# PIC32MZ.net
KiCad netlist of a schematic drawn in Altium Designer
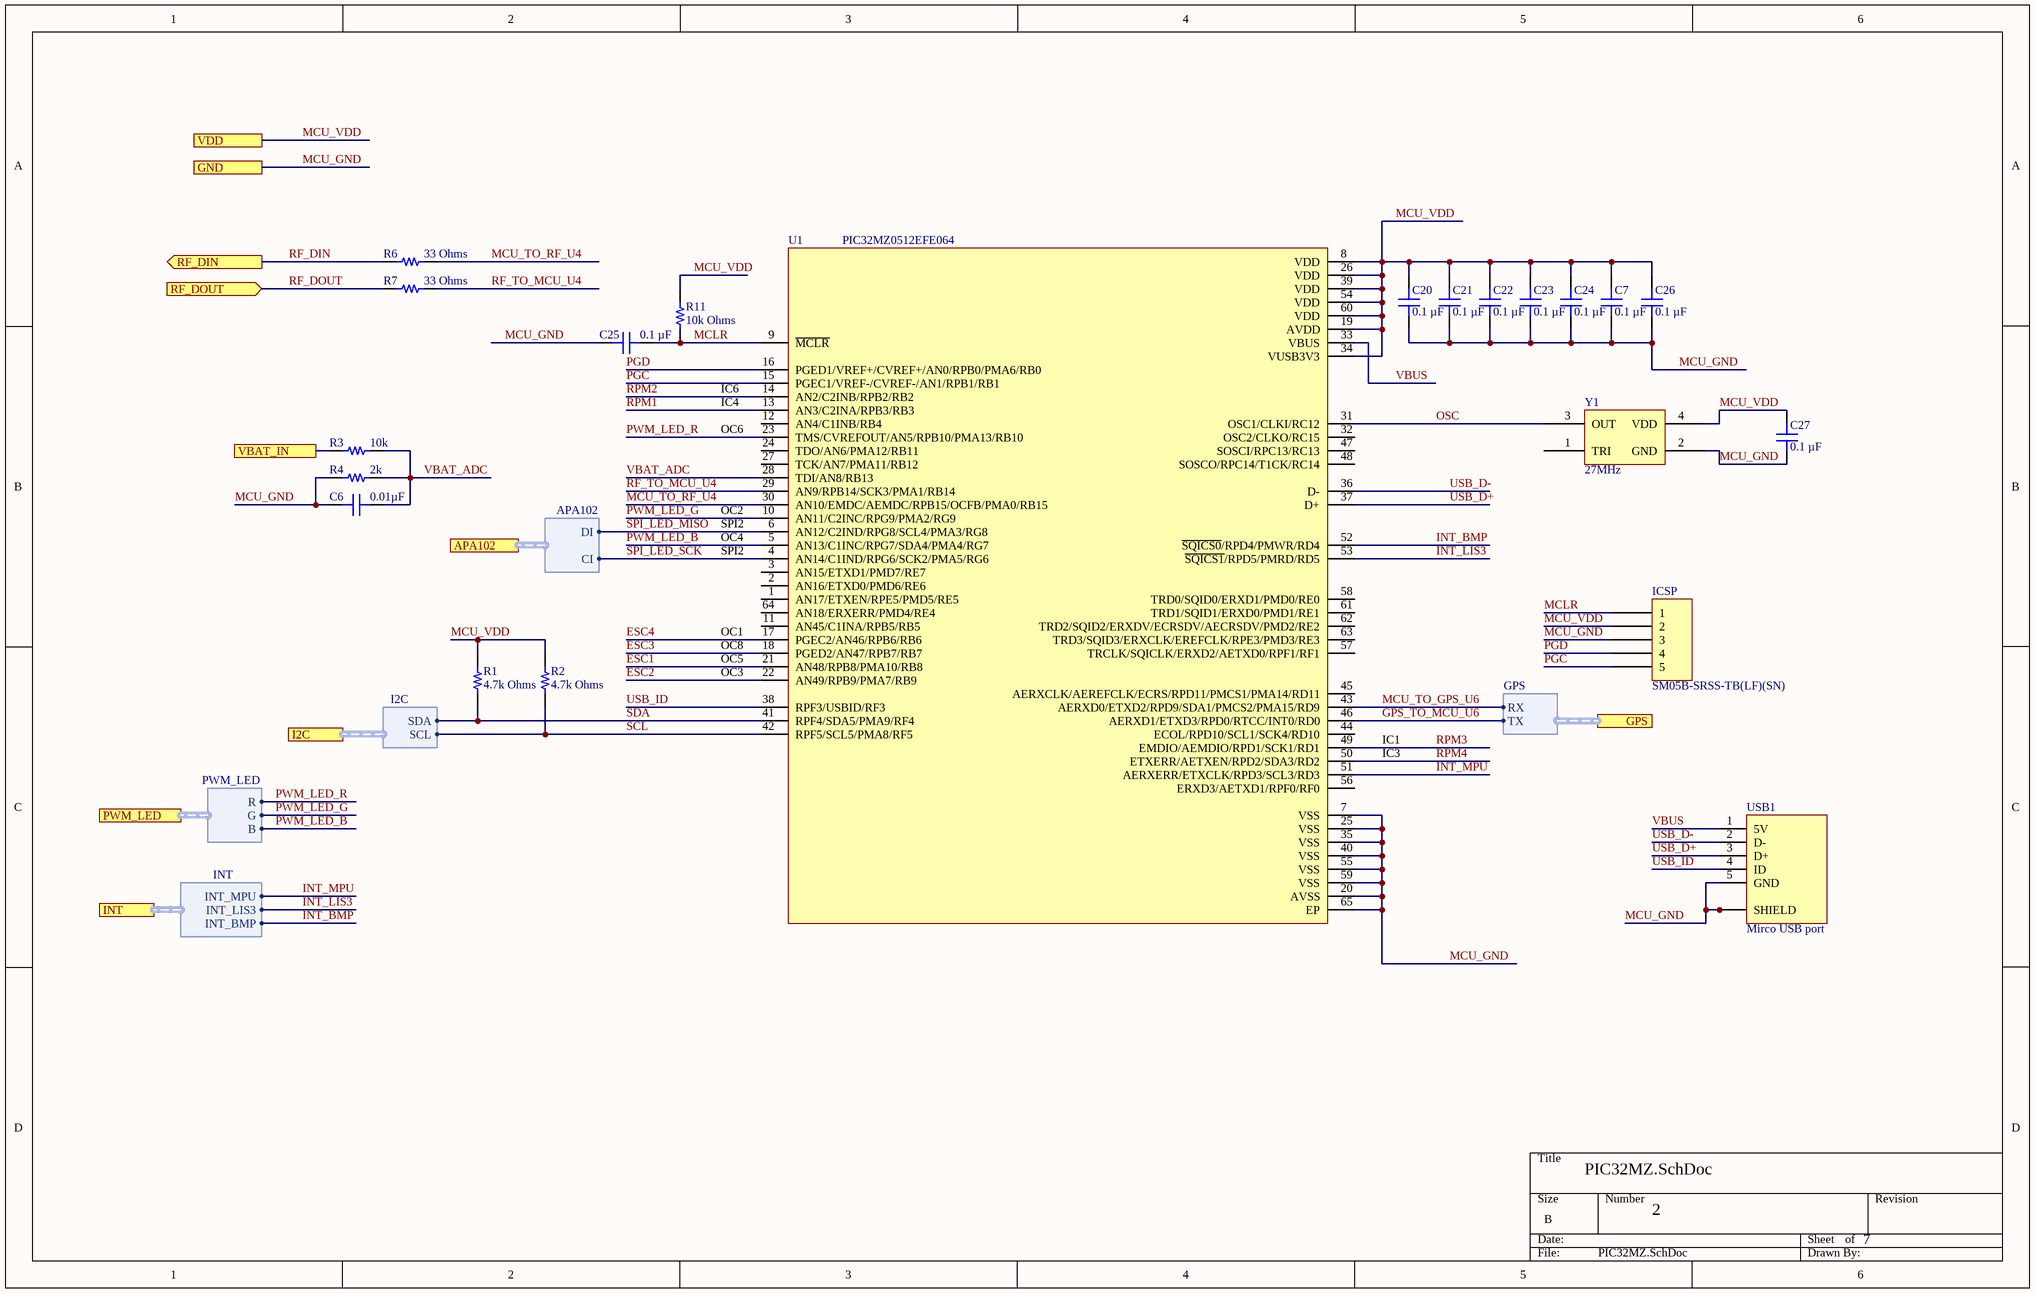
[diagram p0: PIC32MZ.SchDoc]

(export (version "E")
  (design (tool "Eeschema 10.0.6"))
  (components
    (comp (ref "C6")
      (value "0.01µF")
      (footprint "CAP 0603_1608")
      (description "CAP CER 0.1UF 100V 0603 EPOXY")
      (fields
        (field (name "PART NUMBER") "GCG188R92A104KA03D")
        (field (name "MANUFACTURER") "Murata Electronics")
      )
      (libsource (lib "Celestial Altium Library - altium_library") (part "Capacitor"))
    )
    (comp (ref "C7")
      (value "0.1 µF")
      (footprint "CAP 0402_1005")
      (description "CAP CER 0.1UF 16V X7R 0402")
      (fields (field (name "PART NUMBER") "C0402C104K4RACAUTO") (field (name "MANUFACTURER") "KEMET"))
      (libsource (lib "Celestial Altium Library - altium_library") (part "Capacitor"))
    )
    (comp (ref "C20")
      (value "0.1 µF")
      (footprint "CAP 0402_1005")
      (description "CAP CER 0.1UF 16V X7R 0402")
      (fields (field (name "PART NUMBER") "C0402C104K4RACAUTO") (field (name "MANUFACTURER") "KEMET"))
      (libsource (lib "Celestial Altium Library - altium_library") (part "Capacitor"))
    )
    (comp (ref "C21")
      (value "0.1 µF")
      (footprint "CAP 0402_1005")
      (description "CAP CER 0.1UF 16V X7R 0402")
      (fields (field (name "PART NUMBER") "C0402C104K4RACAUTO") (field (name "MANUFACTURER") "KEMET"))
      (libsource (lib "Celestial Altium Library - altium_library") (part "Capacitor"))
    )
    (comp (ref "C22")
      (value "0.1 µF")
      (footprint "CAP 0402_1005")
      (description "CAP CER 0.1UF 16V X7R 0402")
      (fields (field (name "PART NUMBER") "C0402C104K4RACAUTO") (field (name "MANUFACTURER") "KEMET"))
      (libsource (lib "Celestial Altium Library - altium_library") (part "Capacitor"))
    )
    (comp (ref "C23")
      (value "0.1 µF")
      (footprint "CAP 0402_1005")
      (description "CAP CER 0.1UF 16V X7R 0402")
      (fields (field (name "PART NUMBER") "C0402C104K4RACAUTO") (field (name "MANUFACTURER") "KEMET"))
      (libsource (lib "Celestial Altium Library - altium_library") (part "Capacitor"))
    )
    (comp (ref "C24")
      (value "0.1 µF")
      (footprint "CAP 0402_1005")
      (description "CAP CER 0.1UF 16V X7R 0402")
      (fields (field (name "PART NUMBER") "C0402C104K4RACAUTO") (field (name "MANUFACTURER") "KEMET"))
      (libsource (lib "Celestial Altium Library - altium_library") (part "Capacitor"))
    )
    (comp (ref "C25")
      (value "0.1 µF")
      (footprint "CAP 0402_1005")
      (description "CAP CER 0.1UF 16V X7R 0402")
      (fields (field (name "PART NUMBER") "C0402C104K4RACAUTO") (field (name "MANUFACTURER") "KEMET"))
      (libsource (lib "Celestial Altium Library - altium_library") (part "Capacitor"))
    )
    (comp (ref "C26")
      (value "0.1 µF")
      (footprint "CAP 0402_1005")
      (description "CAP CER 0.1UF 16V X7R 0402")
      (fields (field (name "PART NUMBER") "C0402C104K4RACAUTO") (field (name "MANUFACTURER") "KEMET"))
      (libsource (lib "Celestial Altium Library - altium_library") (part "Capacitor"))
    )
    (comp (ref "C27")
      (value "0.1 µF")
      (footprint "CAP 0402_1005")
      (description "CAP CER 0.1UF 16V X7R 0402")
      (fields (field (name "PART NUMBER") "C0402C104K4RACAUTO") (field (name "MANUFACTURER") "KEMET"))
      (libsource (lib "Celestial Altium Library - altium_library") (part "Capacitor"))
    )
    (comp (ref "ICSP")
      (value "SM05B-SRSS-TB(LF)(SN)")
      (footprint "JST SM05B-SRSS-TB")
      (description "CONN HEADER SMD R/A 5POS 1MM")
      (fields (field (name "MANUFACTURER") "JST Sales America Inc."))
      (libsource (lib "Celestial Altium Library - altium_library") (part "5 Pin"))
    )
    (comp (ref "R1")
      (value "4.7k Ohms")
      (footprint "RES 0402_1005")
      (description "RES 330 OHM 5% 1/16W 0402")
      (fields (field (name "PART NUMBER") "CRCW0402330RJNEDC") (field (name "MANUFACTURER") "Vishay Dale"))
      (libsource (lib "Celestial Altium Library - altium_library") (part "Resistor"))
    )
    (comp (ref "R2")
      (value "4.7k Ohms")
      (footprint "RES 0402_1005")
      (description "RES 330 OHM 5% 1/16W 0402")
      (fields (field (name "PART NUMBER") "CRCW0402330RJNEDC") (field (name "MANUFACTURER") "Vishay Dale"))
      (libsource (lib "Celestial Altium Library - altium_library") (part "Resistor"))
    )
    (comp (ref "R3")
      (value "10k")
      (footprint "RES 0603_1608")
      (description "RES SMD 21.5 OHM 1% 1/10W 0603")
      (fields
        (field (name "PART NUMBER") "ERJ-3EKF21R5V")
        (field (name "MANUFACTURER") "Panasonic Electronic Components")
      )
      (libsource (lib "Celestial Altium Library - altium_library") (part "Resistor"))
    )
    (comp (ref "R4")
      (value "2k")
      (footprint "RES 0603_1608")
      (description "RES SMD 21.5 OHM 1% 1/10W 0603")
      (fields
        (field (name "PART NUMBER") "ERJ-3EKF21R5V")
        (field (name "MANUFACTURER") "Panasonic Electronic Components")
      )
      (libsource (lib "Celestial Altium Library - altium_library") (part "Resistor"))
    )
    (comp (ref "R6")
      (value "33 Ohms")
      (footprint "RES 0402_1005")
      (description "RES 330 OHM 5% 1/16W 0402")
      (fields (field (name "PART NUMBER") "CRCW0402330RJNEDC") (field (name "MANUFACTURER") "Vishay Dale"))
      (libsource (lib "Celestial Altium Library - altium_library") (part "Resistor"))
    )
    (comp (ref "R7")
      (value "33 Ohms")
      (footprint "RES 0402_1005")
      (description "RES 330 OHM 5% 1/16W 0402")
      (fields (field (name "PART NUMBER") "CRCW0402330RJNEDC") (field (name "MANUFACTURER") "Vishay Dale"))
      (libsource (lib "Celestial Altium Library - altium_library") (part "Resistor"))
    )
    (comp (ref "R11")
      (value "10k Ohms")
      (footprint "RES 0402_1005")
      (description "RES 330 OHM 5% 1/16W 0402")
      (fields (field (name "PART NUMBER") "CRCW0402330RJNEDC") (field (name "MANUFACTURER") "Vishay Dale"))
      (libsource (lib "Celestial Altium Library - altium_library") (part "Resistor"))
    )
    (comp (ref "U1")
      (value "PIC32MZ0512EFE064")
      (footprint "QFN50P900X900X100-65N")
      (description "32-bit Microcontrollers - MCU 32-BIT MCU 512KB FL 128KB RAM, No Crypto")
      (fields (field (name "MF") "Microchip") (field (name "MP") "PIC32MZ2048EFG064T-I/PT"))
      (libsource (lib "IC") (part "PIC32MZ0512EFE064-I/PT"))
    )
    (comp (ref "USB1")
      (value "Mirco USB port")
      (footprint "AMPHENOL_10118194-0001LF")
      (description "USB - micro B USB 2.0 Receptacle Connector 5 Position Through Hole")
      (fields (field (name "MF") "Amphenol ICC") (field (name "MP") "10118194-0001LF"))
      (libsource (lib "IC") (part "USB Micro Horizontal"))
    )
    (comp (ref "Y1")
      (value "27MHz")
      (footprint "ABRACON ASD")
      (description "XTAL OSC XO 27.0000MHZ HCMOS SMD")
      (fields (field (name "PART NUMBER") "ASD3-27.000MHZ-EC-T") (field (name "MANUFACTURER") "Abracon LLC"))
      (libsource (lib "Celestial Altium Library - altium_library") (part "Abracon XO ASD"))
    )
  )
  (nets
    (net (code "6") (name "/ESC1") (class "Default")
      (node (ref "U1") (pin "21") (pinfunction "AN48/RPB8/PMA10/RB8_21") (pintype "passive"))
    )
    (net (code "7") (name "/ESC2") (class "Default")
      (node (ref "U1") (pin "22") (pinfunction "AN49/RPB9/PMA7/RB9_22") (pintype "passive"))
    )
    (net (code "8") (name "/ESC3") (class "Default")
      (node (ref "U1") (pin "18") (pinfunction "PGED2/AN47/RPB7/RB7_18") (pintype "passive"))
    )
    (net (code "9") (name "/ESC4") (class "Default")
      (node (ref "U1") (pin "17") (pinfunction "PGEC2/AN46/RPB6/RB6_17") (pintype "passive"))
    )
    (net (code "10") (name "/GPS_TO_MCU_U6") (class "Default")
      (node (ref "U1") (pin "46") (pinfunction "AERXD1/ETXD3/RPD0/RTCC/INT0/RD0_46") (pintype "passive"))
    )
    (net (code "11") (name "/INT_BMP") (class "Default")
      (node (ref "U1") (pin "52") (pinfunction "~{SQICS0}/RPD4/PMWR/RD4_52") (pintype "passive"))
    )
    (net (code "12") (name "/INT_LIS3") (class "Default")
      (node (ref "U1") (pin "53") (pinfunction "~{SQICS1}/RPD5/PMRD/RD5_53") (pintype "passive"))
    )
    (net (code "13") (name "/INT_MPU") (class "Default")
      (node (ref "U1") (pin "51") (pinfunction "AERXERR/ETXCLK/RPD3/SCL3/RD3_51") (pintype "passive"))
    )
    (net (code "14") (name "/MCLR") (class "Default")
      (node (ref "C25") (pin "1") (pinfunction "1_1") (pintype "passive"))
      (node (ref "ICSP") (pin "1") (pinfunction "1_1") (pintype "passive"))
      (node (ref "R11") (pin "1") (pinfunction "1_1") (pintype "passive"))
      (node (ref "U1") (pin "9") (pinfunction "~{MCLR}_9") (pintype "passive"))
    )
    (net (code "15") (name "/MCU_GND") (class "Default")
      (node (ref "C20") (pin "1") (pinfunction "1_1") (pintype "passive"))
      (node (ref "C21") (pin "1") (pinfunction "1_1") (pintype "passive"))
      (node (ref "C22") (pin "1") (pinfunction "1_1") (pintype "passive"))
      (node (ref "C23") (pin "1") (pinfunction "1_1") (pintype "passive"))
      (node (ref "C24") (pin "1") (pinfunction "1_1") (pintype "passive"))
      (node (ref "C25") (pin "2") (pinfunction "2_2") (pintype "passive"))
      (node (ref "C26") (pin "1") (pinfunction "1_1") (pintype "passive"))
      (node (ref "C27") (pin "1") (pinfunction "1_1") (pintype "passive"))
      (node (ref "C6") (pin "2") (pinfunction "2_2") (pintype "passive"))
      (node (ref "C7") (pin "1") (pinfunction "1_1") (pintype "passive"))
      (node (ref "ICSP") (pin "3") (pinfunction "3_3") (pintype "passive"))
      (node (ref "R4") (pin "1") (pinfunction "1_1") (pintype "passive"))
      (node (ref "U1") (pin "20") (pinfunction "AVSS_20") (pintype "power_in"))
      (node (ref "U1") (pin "25") (pinfunction "VSS_25") (pintype "power_in"))
      (node (ref "U1") (pin "35") (pinfunction "VSS_35") (pintype "power_in"))
      (node (ref "U1") (pin "40") (pinfunction "VSS_40") (pintype "power_in"))
      (node (ref "U1") (pin "55") (pinfunction "VSS_55") (pintype "power_in"))
      (node (ref "U1") (pin "59") (pinfunction "VSS_59") (pintype "power_in"))
      (node (ref "U1") (pin "65") (pinfunction "EP_65") (pintype "power_in"))
      (node (ref "U1") (pin "7") (pinfunction "VSS_7") (pintype "power_in"))
      (node (ref "USB1") (pin "5") (pinfunction "GND_5") (pintype "passive"))
      (node (ref "USB1") (pin "S1") (pinfunction "SHIELD_S1") (pintype "passive"))
      (node (ref "USB1") (pin "S2") (pinfunction "SHIELD_S2") (pintype "passive"))
      (node (ref "Y1") (pin "2") (pinfunction "GND_2") (pintype "passive"))
    )
    (net (code "16") (name "/MCU_TO_GPS_U6") (class "Default")
      (node (ref "U1") (pin "43") (pinfunction "AERXD0/ETXD2/RPD9/SDA1/PMCS2/PMA15/RD9_43") (pintype "passive"))
    )
    (net (code "17") (name "/MCU_TO_RF_U4") (class "Default")
      (node (ref "R6") (pin "2") (pinfunction "2_2") (pintype "passive"))
      (node (ref "U1") (pin "30") (pinfunction "AN10/EMDC/AEMDC/RPB15/OCFB/PMA0/RB15_30") (pintype "passive"))
    )
    (net (code "18") (name "/MCU_VDD") (class "Default")
      (node (ref "C20") (pin "2") (pinfunction "2_2") (pintype "passive"))
      (node (ref "C21") (pin "2") (pinfunction "2_2") (pintype "passive"))
      (node (ref "C22") (pin "2") (pinfunction "2_2") (pintype "passive"))
      (node (ref "C23") (pin "2") (pinfunction "2_2") (pintype "passive"))
      (node (ref "C24") (pin "2") (pinfunction "2_2") (pintype "passive"))
      (node (ref "C26") (pin "2") (pinfunction "2_2") (pintype "passive"))
      (node (ref "C27") (pin "2") (pinfunction "2_2") (pintype "passive"))
      (node (ref "C7") (pin "2") (pinfunction "2_2") (pintype "passive"))
      (node (ref "ICSP") (pin "2") (pinfunction "2_2") (pintype "passive"))
      (node (ref "R1") (pin "2") (pinfunction "2_2") (pintype "passive"))
      (node (ref "R11") (pin "2") (pinfunction "2_2") (pintype "passive"))
      (node (ref "R2") (pin "2") (pinfunction "2_2") (pintype "passive"))
      (node (ref "U1") (pin "19") (pinfunction "AVDD_19") (pintype "power_in"))
      (node (ref "U1") (pin "26") (pinfunction "VDD_26") (pintype "power_in"))
      (node (ref "U1") (pin "34") (pinfunction "VUSB3V3_34") (pintype "power_in"))
      (node (ref "U1") (pin "39") (pinfunction "VDD_39") (pintype "power_in"))
      (node (ref "U1") (pin "54") (pinfunction "VDD_54") (pintype "power_in"))
      (node (ref "U1") (pin "60") (pinfunction "VDD_60") (pintype "power_in"))
      (node (ref "U1") (pin "8") (pinfunction "VDD_8") (pintype "power_in"))
      (node (ref "Y1") (pin "4") (pinfunction "VDD_4") (pintype "passive"))
    )
    (net (code "19") (name "/OSC") (class "Default")
      (node (ref "U1") (pin "31") (pinfunction "OSC1/CLKI/RC12_31") (pintype "passive"))
      (node (ref "Y1") (pin "3") (pinfunction "OUT_3") (pintype "passive"))
    )
    (net (code "20") (name "/PGC") (class "Default")
      (node (ref "ICSP") (pin "5") (pinfunction "5_5") (pintype "passive"))
      (node (ref "U1") (pin "15") (pinfunction "PGEC1/VREF-/CVREF-/AN1/RPB1/RB1_15") (pintype "passive"))
    )
    (net (code "21") (name "/PGD") (class "Default")
      (node (ref "ICSP") (pin "4") (pinfunction "4_4") (pintype "passive"))
      (node (ref "U1") (pin "16") (pinfunction "PGED1/VREF+/CVREF+/AN0/RPB0/PMA6/RB0_16") (pintype "passive"))
    )
    (net (code "22") (name "/PWM_LED_B") (class "Default")
      (node (ref "U1") (pin "5") (pinfunction "AN13/C1INC/RPG7/SDA4/PMA4/RG7_5") (pintype "passive"))
    )
    (net (code "23") (name "/PWM_LED_G") (class "Default")
      (node (ref "U1") (pin "10") (pinfunction "AN11/C2INC/RPG9/PMA2/RG9_10") (pintype "passive"))
    )
    (net (code "24") (name "/PWM_LED_R") (class "Default")
      (node (ref "U1") (pin "23") (pinfunction "TMS/CVREFOUT/AN5/RPB10/PMA13/RB10_23") (pintype "passive"))
    )
    (net (code "25") (name "/RF_DIN") (class "Default")
      (node (ref "R6") (pin "1") (pinfunction "1_1") (pintype "passive"))
    )
    (net (code "26") (name "/RF_DOUT") (class "Default")
      (node (ref "R7") (pin "1") (pinfunction "1_1") (pintype "passive"))
    )
    (net (code "27") (name "/RF_TO_MCU_U4") (class "Default")
      (node (ref "R7") (pin "2") (pinfunction "2_2") (pintype "passive"))
      (node (ref "U1") (pin "29") (pinfunction "AN9/RPB14/SCK3/PMA1/RB14_29") (pintype "passive"))
    )
    (net (code "28") (name "/RPM1") (class "Default")
      (node (ref "U1") (pin "13") (pinfunction "AN3/C2INA/RPB3/RB3_13") (pintype "passive"))
    )
    (net (code "29") (name "/RPM2") (class "Default")
      (node (ref "U1") (pin "14") (pinfunction "AN2/C2INB/RPB2/RB2_14") (pintype "passive"))
    )
    (net (code "30") (name "/RPM3") (class "Default")
      (node (ref "U1") (pin "49") (pinfunction "EMDIO/AEMDIO/RPD1/SCK1/RD1_49") (pintype "passive"))
    )
    (net (code "31") (name "/RPM4") (class "Default")
      (node (ref "U1") (pin "50") (pinfunction "ETXERR/AETXEN/RPD2/SDA3/RD2_50") (pintype "passive"))
    )
    (net (code "32") (name "/SCL") (class "Default")
      (node (ref "R2") (pin "1") (pinfunction "1_1") (pintype "passive"))
      (node (ref "U1") (pin "42") (pinfunction "RPF5/SCL5/PMA8/RF5_42") (pintype "passive"))
    )
    (net (code "33") (name "/SDA") (class "Default")
      (node (ref "R1") (pin "1") (pinfunction "1_1") (pintype "passive"))
      (node (ref "U1") (pin "41") (pinfunction "RPF4/SDA5/PMA9/RF4_41") (pintype "passive"))
    )
    (net (code "34") (name "/SPI_LED_MISO") (class "Default")
      (node (ref "U1") (pin "6") (pinfunction "AN12/C2IND/RPG8/SCL4/PMA3/RG8_6") (pintype "passive"))
    )
    (net (code "35") (name "/SPI_LED_SCK") (class "Default")
      (node (ref "U1") (pin "4") (pinfunction "AN14/C1IND/RPG6/SCK2/PMA5/RG6_4") (pintype "passive"))
    )
    (net (code "36") (name "/USB_D+") (class "Default")
      (node (ref "U1") (pin "37") (pinfunction "D+_37") (pintype "passive"))
      (node (ref "USB1") (pin "3") (pinfunction "D+_3") (pintype "passive"))
    )
    (net (code "37") (name "/USB_D-") (class "Default")
      (node (ref "U1") (pin "36") (pinfunction "D-_36") (pintype "passive"))
      (node (ref "USB1") (pin "2") (pinfunction "D-_2") (pintype "passive"))
    )
    (net (code "38") (name "/USB_ID") (class "Default")
      (node (ref "U1") (pin "38") (pinfunction "RPF3/USBID/RF3_38") (pintype "passive"))
      (node (ref "USB1") (pin "4") (pinfunction "ID_4") (pintype "passive"))
    )
    (net (code "39") (name "/VBAT_ADC") (class "Default")
      (node (ref "C6") (pin "1") (pinfunction "1_1") (pintype "passive"))
      (node (ref "R3") (pin "1") (pinfunction "1_1") (pintype "passive"))
      (node (ref "R4") (pin "2") (pinfunction "2_2") (pintype "passive"))
      (node (ref "U1") (pin "28") (pinfunction "TDI/AN8/RB13_28") (pintype "passive"))
    )
    (net (code "40") (name "/VBAT_IN") (class "Default")
      (node (ref "R3") (pin "2") (pinfunction "2_2") (pintype "passive"))
    )
    (net (code "41") (name "/VBUS") (class "Default")
      (node (ref "U1") (pin "33") (pinfunction "VBUS_33") (pintype "power_in"))
      (node (ref "USB1") (pin "1") (pinfunction "5V_1") (pintype "passive"))
    )
    (net (code "47") (name "unconnected-(U1-AERXCLK{slash}AEREFCLK{slash}ECRS{slash}RPD11{slash}PMCS1{slash}PMA14{slash}RD11-Pad45)") (class "Default")
      (node (ref "U1") (pin "45") (pinfunction "AERXCLK/AEREFCLK/ECRS/RPD11/PMCS1/PMA14/RD11_45") (pintype "passive"))
    )
    (net (code "48") (name "unconnected-(U1-AN4{slash}C1INB{slash}RB4-Pad12)") (class "Default")
      (node (ref "U1") (pin "12") (pinfunction "AN4/C1INB/RB4_12") (pintype "passive"))
    )
    (net (code "49") (name "unconnected-(U1-AN15{slash}ETXD1{slash}PMD7{slash}RE7-Pad3)") (class "Default")
      (node (ref "U1") (pin "3") (pinfunction "AN15/ETXD1/PMD7/RE7_3") (pintype "passive"))
    )
    (net (code "50") (name "unconnected-(U1-AN16{slash}ETXD0{slash}PMD6{slash}RE6-Pad2)") (class "Default")
      (node (ref "U1") (pin "2") (pinfunction "AN16/ETXD0/PMD6/RE6_2") (pintype "passive"))
    )
    (net (code "51") (name "unconnected-(U1-AN17{slash}ETXEN{slash}RPE5{slash}PMD5{slash}RE5-Pad1)") (class "Default")
      (node (ref "U1") (pin "1") (pinfunction "AN17/ETXEN/RPE5/PMD5/RE5_1") (pintype "passive"))
    )
    (net (code "52") (name "unconnected-(U1-AN18{slash}ERXERR{slash}PMD4{slash}RE4-Pad64)") (class "Default")
      (node (ref "U1") (pin "64") (pinfunction "AN18/ERXERR/PMD4/RE4_64") (pintype "passive"))
    )
    (net (code "53") (name "unconnected-(U1-AN45{slash}C1INA{slash}RPB5{slash}RB5-Pad11)") (class "Default")
      (node (ref "U1") (pin "11") (pinfunction "AN45/C1INA/RPB5/RB5_11") (pintype "passive"))
    )
    (net (code "54") (name "unconnected-(U1-ECOL{slash}RPD10{slash}SCL1{slash}SCK4{slash}RD10-Pad44)") (class "Default")
      (node (ref "U1") (pin "44") (pinfunction "ECOL/RPD10/SCL1/SCK4/RD10_44") (pintype "passive"))
    )
    (net (code "55") (name "unconnected-(U1-ERXD3{slash}AETXD1{slash}RPF0{slash}RF0-Pad56)") (class "Default")
      (node (ref "U1") (pin "56") (pinfunction "ERXD3/AETXD1/RPF0/RF0_56") (pintype "passive"))
    )
    (net (code "56") (name "unconnected-(U1-OSC2{slash}CLKO{slash}RC15-Pad32)") (class "Default")
      (node (ref "U1") (pin "32") (pinfunction "OSC2/CLKO/RC15_32") (pintype "passive"))
    )
    (net (code "57") (name "unconnected-(U1-SOSCI{slash}RPC13{slash}RC13-Pad47)") (class "Default")
      (node (ref "U1") (pin "47") (pinfunction "SOSCI/RPC13/RC13_47") (pintype "passive"))
    )
    (net (code "58") (name "unconnected-(U1-SOSCO{slash}RPC14{slash}T1CK{slash}RC14-Pad48)") (class "Default")
      (node (ref "U1") (pin "48") (pinfunction "SOSCO/RPC14/T1CK/RC14_48") (pintype "passive"))
    )
    (net (code "59") (name "unconnected-(U1-TCK{slash}AN7{slash}PMA11{slash}RB12-Pad27)") (class "Default")
      (node (ref "U1") (pin "27") (pinfunction "TCK/AN7/PMA11/RB12_27") (pintype "passive"))
    )
    (net (code "60") (name "unconnected-(U1-TDO{slash}AN6{slash}PMA12{slash}RB11-Pad24)") (class "Default")
      (node (ref "U1") (pin "24") (pinfunction "TDO/AN6/PMA12/RB11_24") (pintype "passive"))
    )
    (net (code "61") (name "unconnected-(U1-TRCLK{slash}SQICLK{slash}ERXD2{slash}AETXD0{slash}RPF1{slash}RF1-Pad57)") (class "Default")
      (node (ref "U1") (pin "57") (pinfunction "TRCLK/SQICLK/ERXD2/AETXD0/RPF1/RF1_57") (pintype "passive"))
    )
    (net (code "62") (name "unconnected-(U1-TRD0{slash}SQID0{slash}ERXD1{slash}PMD0{slash}RE0-Pad58)") (class "Default")
      (node (ref "U1") (pin "58") (pinfunction "TRD0/SQID0/ERXD1/PMD0/RE0_58") (pintype "passive"))
    )
    (net (code "63") (name "unconnected-(U1-TRD1{slash}SQID1{slash}ERXD0{slash}PMD1{slash}RE1-Pad61)") (class "Default")
      (node (ref "U1") (pin "61") (pinfunction "TRD1/SQID1/ERXD0/PMD1/RE1_61") (pintype "passive"))
    )
    (net (code "64") (name "unconnected-(U1-TRD2{slash}SQID2{slash}ERXDV{slash}ECRSDV{slash}AECRSDV{slash}PMD2{slash}RE2-Pad62)") (class "Default")
      (node (ref "U1") (pin "62") (pinfunction "TRD2/SQID2/ERXDV/ECRSDV/AECRSDV/PMD2/RE2_62") (pintype "passive"))
    )
    (net (code "65") (name "unconnected-(U1-TRD3{slash}SQID3{slash}ERXCLK{slash}EREFCLK{slash}RPE3{slash}PMD3{slash}RE3-Pad63)") (class "Default")
      (node (ref "U1") (pin "63") (pinfunction "TRD3/SQID3/ERXCLK/EREFCLK/RPE3/PMD3/RE3_63") (pintype "passive"))
    )
    (net (code "66") (name "unconnected-(Y1-TRI-Pad1)") (class "Default")
      (node (ref "Y1") (pin "1") (pinfunction "TRI_1") (pintype "passive"))
    )
  )
)
